# AQ_sensor_GSM.net
KiCad netlist of a schematic drawn in EAGLE
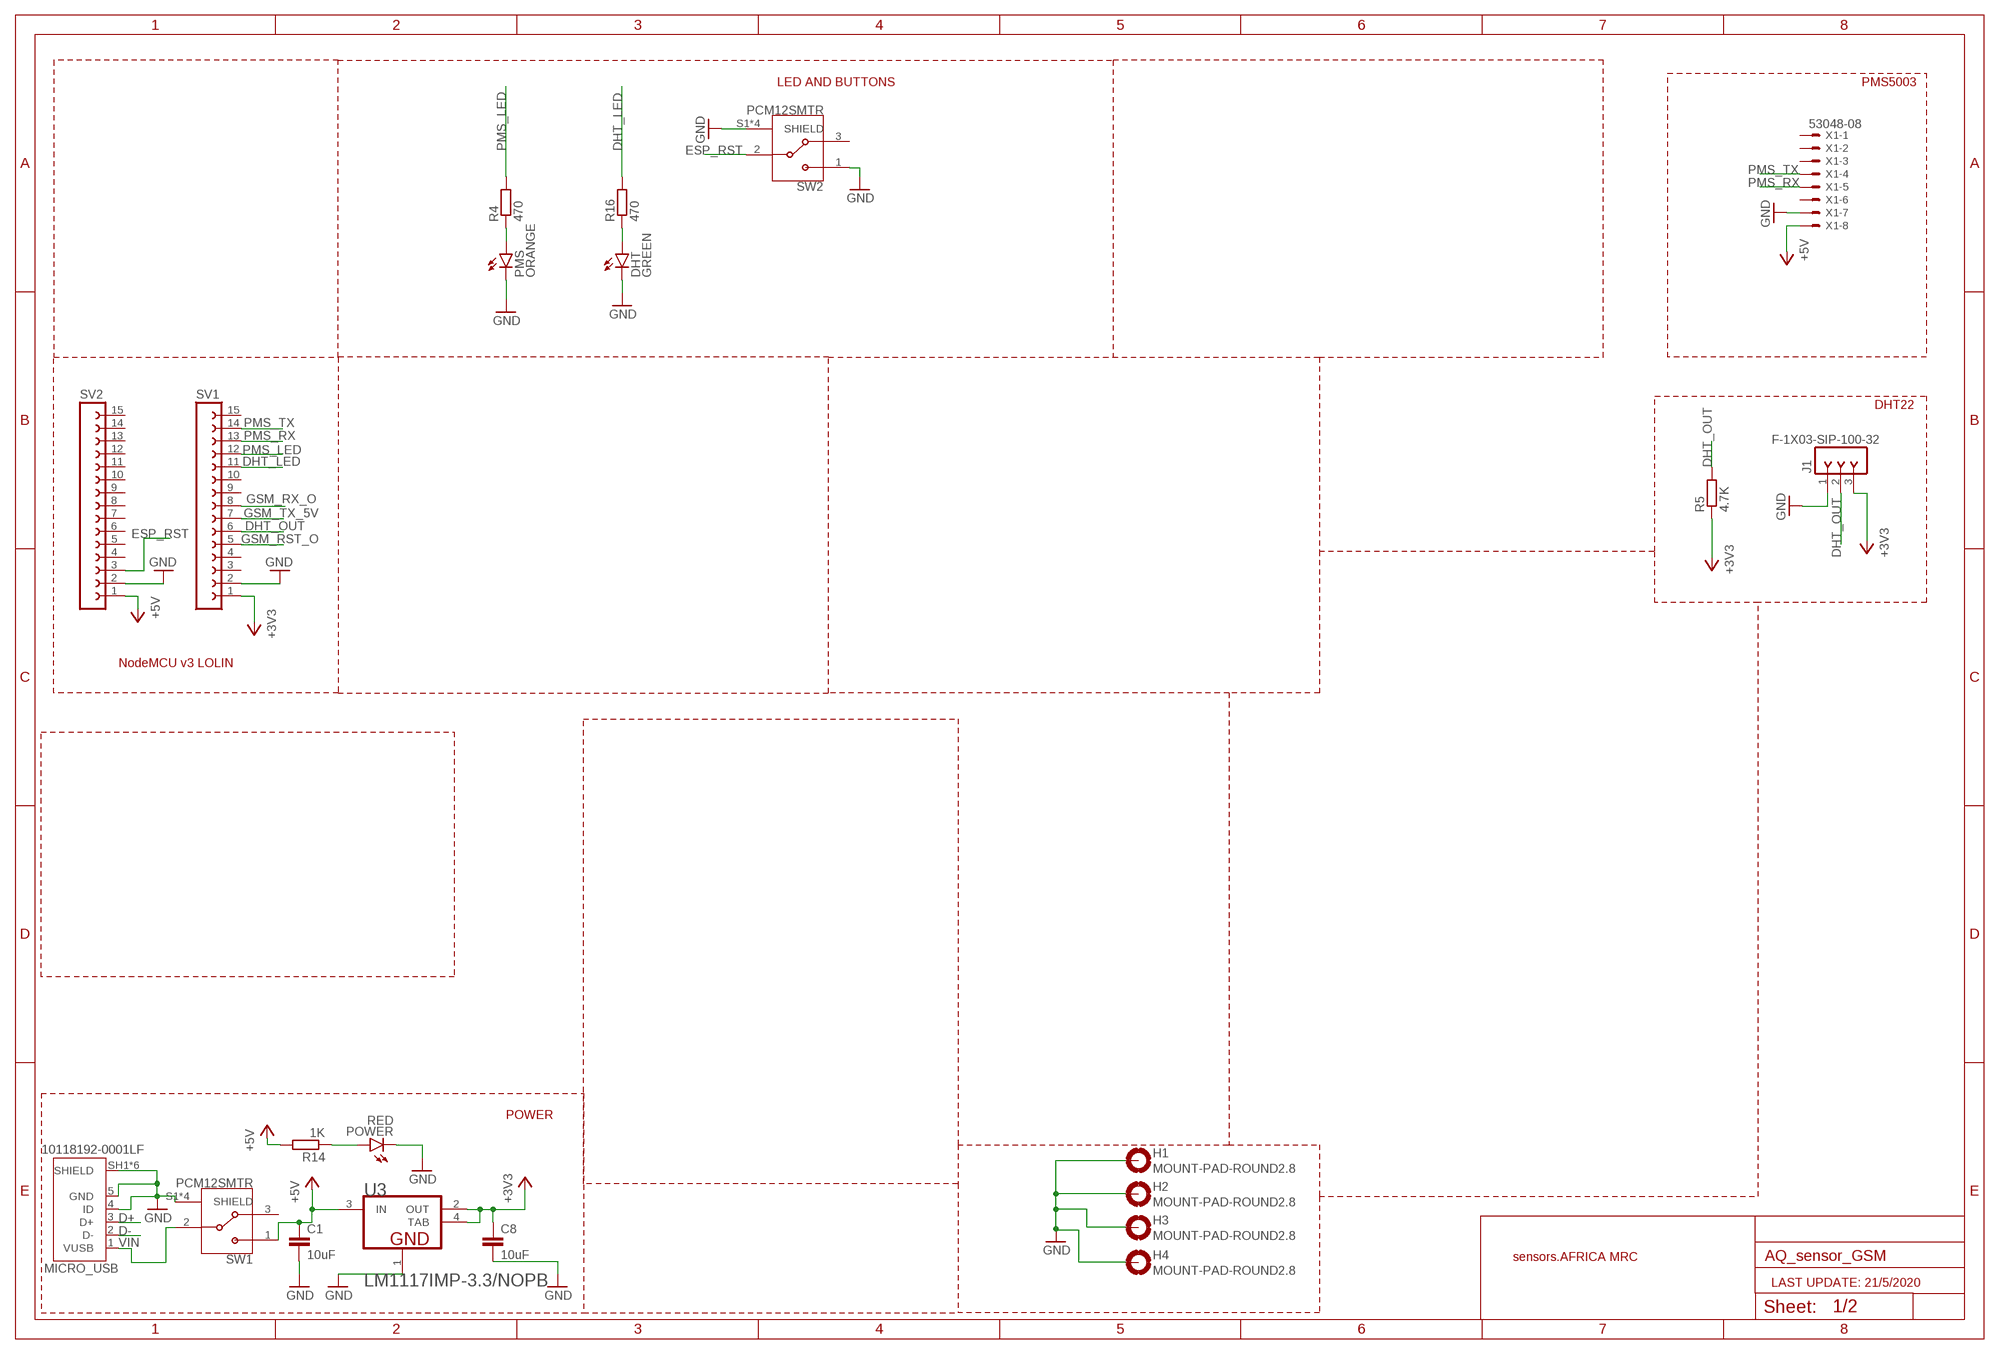
[diagram p0: schematic, sheet 1]
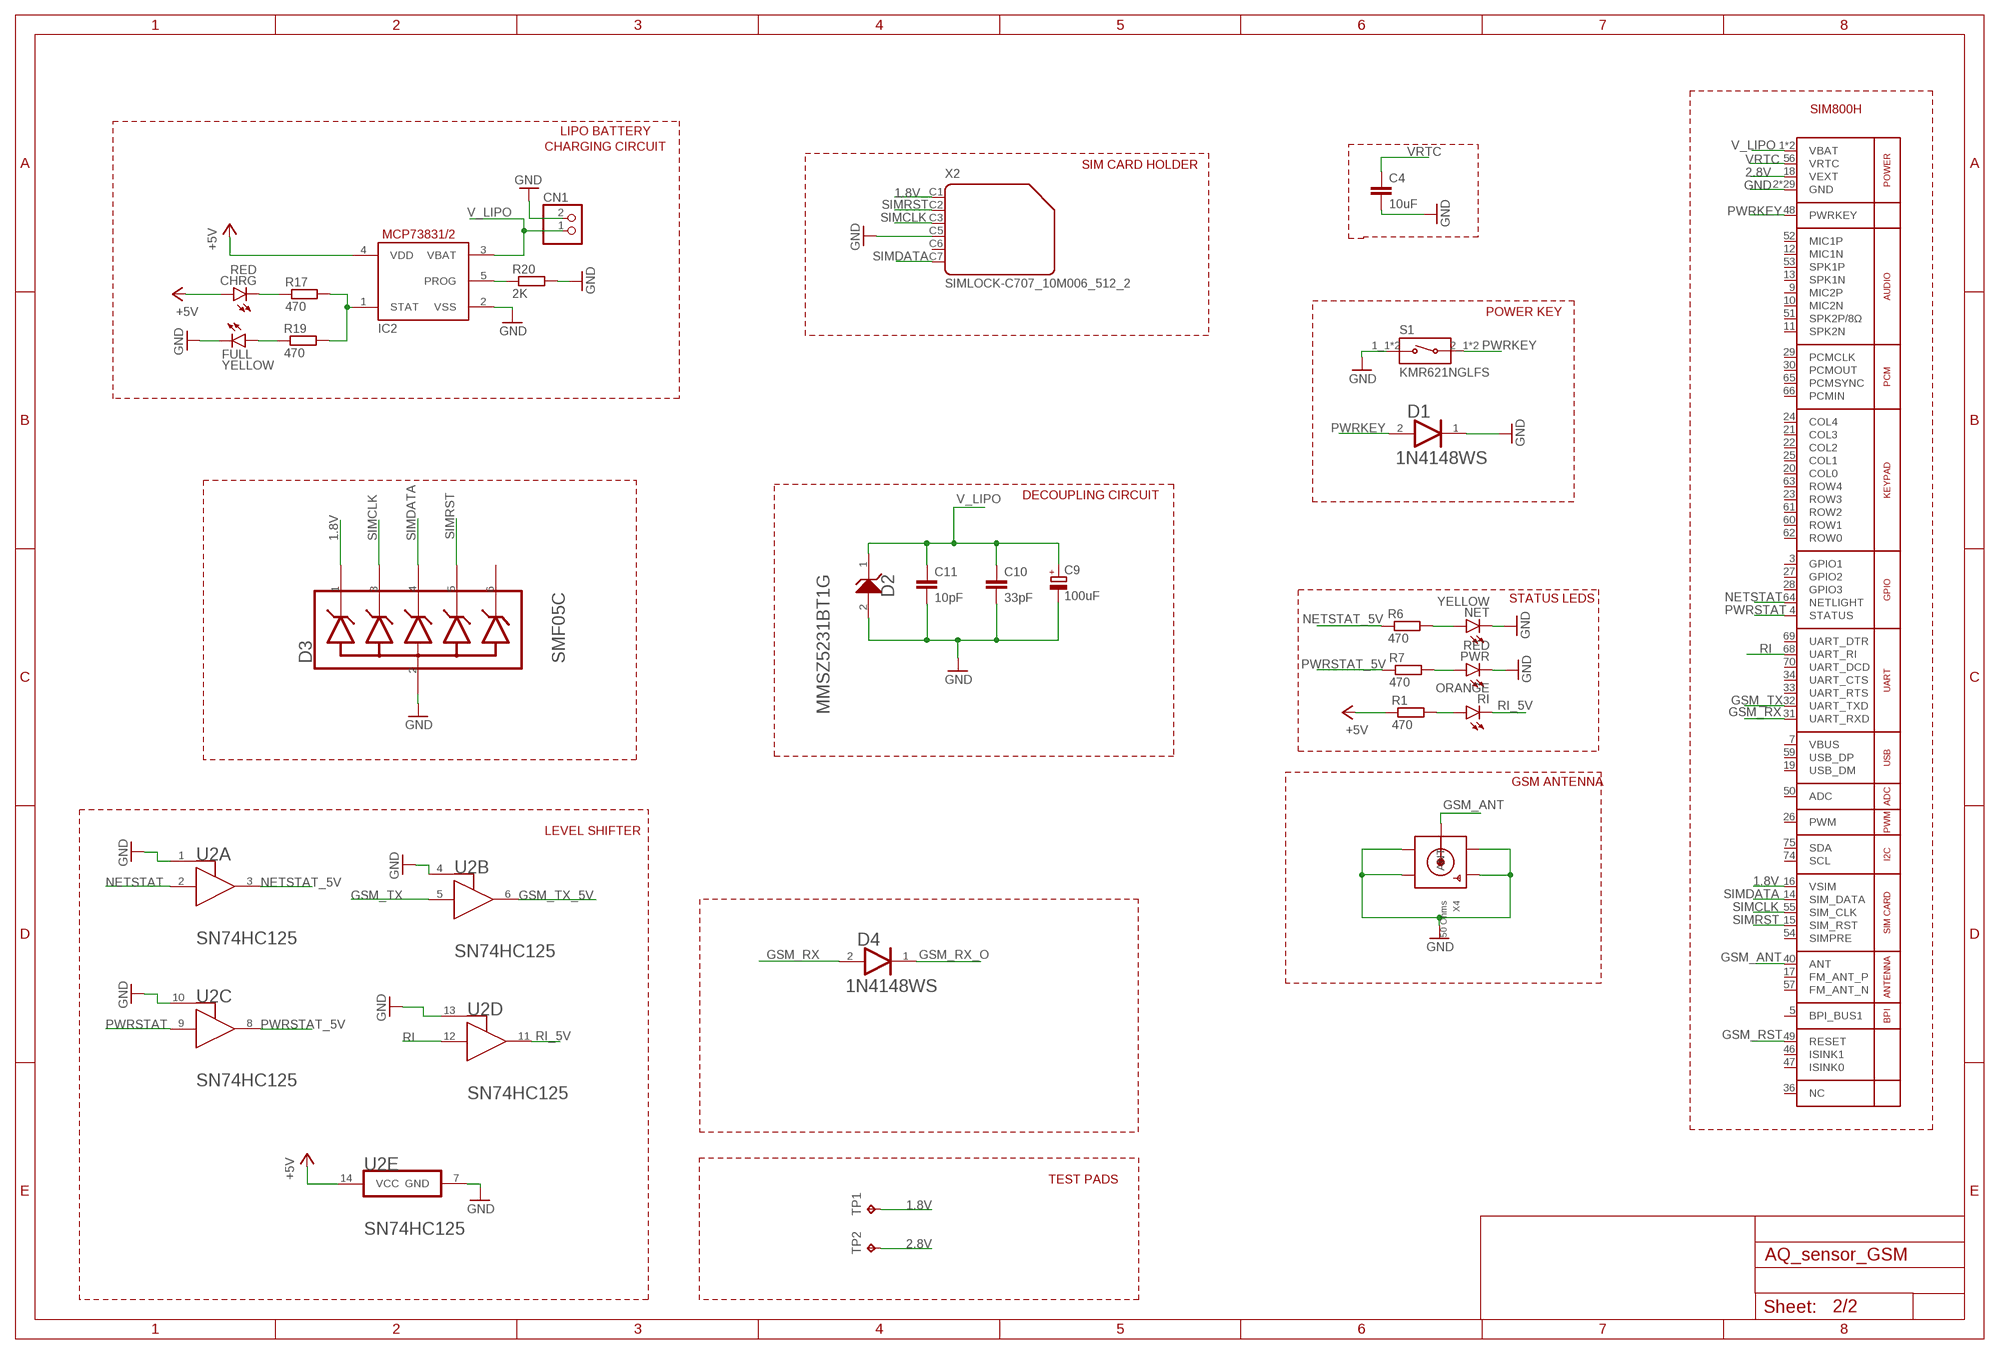
[diagram p1: schematic, sheet 2]

(export (version "E")
  (design (tool "Eeschema 10.0.6"))
  (components
    (comp (ref "C1")
      (value "10uF")
      (footprint "eagle-import:C0603")
      (libsource (lib "eagle-import") (part "C-EUC0603"))
    )
    (comp (ref "C8")
      (value "10uF")
      (footprint "eagle-import:C0603")
      (libsource (lib "eagle-import") (part "C-EUC0603"))
    )
    (comp (ref "DHT")
      (value "GREEN")
      (footprint "eagle-import:CHIP-LED0603")
      (libsource (lib "eagle-import") (part "LEDCHIP-LED0603"))
    )
    (comp (ref "H1")
      (value "MOUNT-PAD-ROUND2.8")
      (footprint "eagle-import:2,8-PAD")
      (libsource (lib "eagle-import") (part "MOUNT-PAD-ROUND2.8"))
    )
    (comp (ref "H2")
      (value "MOUNT-PAD-ROUND2.8")
      (footprint "eagle-import:2,8-PAD")
      (libsource (lib "eagle-import") (part "MOUNT-PAD-ROUND2.8"))
    )
    (comp (ref "H3")
      (value "MOUNT-PAD-ROUND2.8")
      (footprint "eagle-import:2,8-PAD")
      (libsource (lib "eagle-import") (part "MOUNT-PAD-ROUND2.8"))
    )
    (comp (ref "H4")
      (value "MOUNT-PAD-ROUND2.8")
      (footprint "eagle-import:2,8-PAD")
      (libsource (lib "eagle-import") (part "MOUNT-PAD-ROUND2.8"))
    )
    (comp (ref "J1")
      (value "F-1X03-SIP-100-32")
      (footprint "eagle-import:SIP-100-03-32")
      (libsource (lib "eagle-import") (part "F-1X03-SIP-100-32"))
    )
    (comp (ref "MICRO_USB")
      (value "10118192-0001LF")
      (footprint "eagle-import:AMPHENOL_10118192-0001LF")
      (fields (field (name "MF") "Amphenol ICC"))
      (libsource (lib "eagle-import") (part "10118192-0001LF"))
    )
    (comp (ref "PMS")
      (value "ORANGE")
      (footprint "eagle-import:CHIP-LED0603")
      (libsource (lib "eagle-import") (part "LEDCHIP-LED0603"))
    )
    (comp (ref "POWER")
      (value "RED")
      (footprint "eagle-import:CHIP-LED0603")
      (libsource (lib "eagle-import") (part "LEDCHIP-LED0603"))
    )
    (comp (ref "R4")
      (value "470")
      (footprint "eagle-import:R0603")
      (libsource (lib "eagle-import") (part "R-EU_R0603"))
    )
    (comp (ref "R5")
      (value "4.7K")
      (footprint "eagle-import:R0603")
      (libsource (lib "eagle-import") (part "R-EU_R0603"))
    )
    (comp (ref "R14")
      (value "1K")
      (footprint "eagle-import:R0603")
      (libsource (lib "eagle-import") (part "R-EU_R0603"))
    )
    (comp (ref "R16")
      (value "470")
      (footprint "eagle-import:R0603")
      (libsource (lib "eagle-import") (part "R-EU_R0603"))
    )
    (comp (ref "SV1")
      (value "FE15-1")
      (footprint "eagle-import:FE15")
      (libsource (lib "eagle-import") (part "FE15-1"))
    )
    (comp (ref "SV2")
      (value "FE15-1")
      (footprint "eagle-import:FE15")
      (libsource (lib "eagle-import") (part "FE15-1"))
    )
    (comp (ref "SW1")
      (value "PCM12SMTR")
      (footprint "eagle-import:SW_PCM12SMTR")
      (fields (field (name "MF") "C&K"))
      (libsource (lib "eagle-import") (part "PCM12SMTR"))
    )
    (comp (ref "SW2")
      (value "PCM12SMTR")
      (footprint "eagle-import:SW_PCM12SMTR")
      (fields (field (name "MF") "C&K"))
      (libsource (lib "eagle-import") (part "PCM12SMTR"))
    )
    (comp (ref "U3")
      (value "TEXAS_INSTRUMENTS_LM1117IMP-3.3-NOPBTEXAS_INSTRUMENTS_LM1117IMP-3.3-NOPB_0_0")
      (footprint "eagle-import:TEXAS_INSTRUMENTS_LM1117IMP-3.3-NOPB_0")
      (fields (field (name "MF") "Texas Instruments") (field (name "MPN") "LM1117IMP-3.3/NOPB"))
      (libsource (lib "eagle-import") (part "TEXAS_INSTRUMENTS_LM1117IMP-3.3-NOPBTEXAS_INSTRUMENTS_LM1117IMP-3.3-NOPB_0_0"))
    )
    (comp (ref "X1")
      (value "53048-08")
      (footprint "eagle-import:53048-08")
      (fields (field (name "MF") "WALDOM/MOLEX") (field (name "MPN") "53048-0810"))
      (libsource (lib "eagle-import") (part "53?-08048"))
    )
    (comp (ref "C4")
      (value "10uF")
      (footprint "eagle-import:C0603")
      (libsource (lib "eagle-import") (part "C-EUC0603"))
    )
    (comp (ref "C9")
      (value "100uF")
      (footprint "eagle-import:PANASONIC_D")
      (libsource (lib "eagle-import") (part "CPOL-EUD"))
    )
    (comp (ref "C10")
      (value "33pF")
      (footprint "eagle-import:C0603")
      (libsource (lib "eagle-import") (part "C-EUC0603"))
    )
    (comp (ref "C11")
      (value "10pF")
      (footprint "eagle-import:C0603")
      (libsource (lib "eagle-import") (part "C-EUC0603"))
    )
    (comp (ref "CHRG")
      (value "RED")
      (footprint "eagle-import:CHIP-LED0603")
      (libsource (lib "eagle-import") (part "LEDCHIP-LED0603"))
    )
    (comp (ref "CN1")
      (value "JST_2PIN-SMT-RA")
      (footprint "eagle-import:JST-PH-2-SMT-RA")
      (libsource (lib "eagle-import") (part "JST_2PIN-SMT-RA"))
    )
    (comp (ref "D1")
      (value "ON_SEMI_1N4148WSON_SEMI_1N4148WS_0_0")
      (footprint "eagle-import:ON_SEMI_1N4148WS_0")
      (fields
        (field (name "DIGIKEY_PART_NUMBER") "1N4148WSFSCT-ND")
        (field (name "MF") "ON Semi")
        (field (name "MOUSER_PART_NUMBER") "512-1N4148WS")
      )
      (libsource (lib "eagle-import") (part "ON_SEMI_1N4148WSON_SEMI_1N4148WS_0_0"))
    )
    (comp (ref "D2")
      (value "ON_SEMICONDUCTOR_MMSZ5231BT1GON_SEMICONDUCTOR_MMSZ5231BT1G_0_0")
      (footprint "eagle-import:ON_SEMICONDUCTOR_MMSZ5231BT1G_0")
      (fields (field (name "MF") "On Semiconductor") (field (name "MPN") "MMSZ5231BT1G"))
      (libsource (lib "eagle-import") (part "ON_SEMICONDUCTOR_MMSZ5231BT1GON_SEMICONDUCTOR_MMSZ5231BT1G_0_0"))
    )
    (comp (ref "D3")
      (value "SEMTECH_SMF05CSEMTECH_SMF05C_0_0")
      (footprint "eagle-import:SEMTECH_SMF05C_0")
      (fields
        (field (name "DIGIKEY_PART_NUMBER") "SMF05CCT-ND")
        (field (name "MF") "Semtech")
        (field (name "MOUSER_PART_NUMBER") "947-SMF05C.TCT")
      )
      (libsource (lib "eagle-import") (part "SEMTECH_SMF05CSEMTECH_SMF05C_0_0"))
    )
    (comp (ref "D4")
      (value "ON_SEMI_1N4148WSON_SEMI_1N4148WS_0_0")
      (footprint "eagle-import:ON_SEMI_1N4148WS_0")
      (fields
        (field (name "DIGIKEY_PART_NUMBER") "1N4148WSFSCT-ND")
        (field (name "MF") "ON Semi")
        (field (name "MOUSER_PART_NUMBER") "512-1N4148WS")
      )
      (libsource (lib "eagle-import") (part "ON_SEMI_1N4148WSON_SEMI_1N4148WS_0_0"))
    )
    (comp (ref "FULL")
      (value "YELLOW")
      (footprint "eagle-import:CHIP-LED0603")
      (libsource (lib "eagle-import") (part "LEDCHIP-LED0603"))
    )
    (comp (ref "IC2")
      (value "MCP73831/OT")
      (footprint "eagle-import:SOT23-5L")
      (libsource (lib "eagle-import") (part "MCP73831/OT"))
    )
    (comp (ref "NET")
      (value "YELLOW")
      (footprint "eagle-import:CHIP-LED0603")
      (libsource (lib "eagle-import") (part "LEDCHIP-LED0603"))
    )
    (comp (ref "PWR")
      (value "RED")
      (footprint "eagle-import:CHIP-LED0603")
      (libsource (lib "eagle-import") (part "LEDCHIP-LED0603"))
    )
    (comp (ref "R1")
      (value "470")
      (footprint "eagle-import:R0603")
      (libsource (lib "eagle-import") (part "R-EU_R0603"))
    )
    (comp (ref "R6")
      (value "470")
      (footprint "eagle-import:R0603")
      (libsource (lib "eagle-import") (part "R-EU_R0603"))
    )
    (comp (ref "R7")
      (value "470")
      (footprint "eagle-import:R0603")
      (libsource (lib "eagle-import") (part "R-EU_R0603"))
    )
    (comp (ref "R17")
      (value "470")
      (footprint "eagle-import:R0603")
      (libsource (lib "eagle-import") (part "R-EU_R0603"))
    )
    (comp (ref "R19")
      (value "470")
      (footprint "eagle-import:R0603")
      (libsource (lib "eagle-import") (part "R-EU_R0603"))
    )
    (comp (ref "R20")
      (value "2K")
      (footprint "eagle-import:R0603")
      (libsource (lib "eagle-import") (part "R-EU_R0603"))
    )
    (comp (ref "RI")
      (value "ORANGE")
      (footprint "eagle-import:CHIP-LED0603")
      (libsource (lib "eagle-import") (part "LEDCHIP-LED0603"))
    )
    (comp (ref "S1")
      (value "KMR621NGLFS")
      (footprint "eagle-import:SW_KMR621NGLFS")
      (fields (field (name "MF") "C&K") (field (name "MP") "KMR621NG LFS"))
      (libsource (lib "eagle-import") (part "KMR621NGLFS"))
    )
    (comp (ref "TP1")
      (value "TPB1,27")
      (footprint "eagle-import:B1,27")
      (libsource (lib "eagle-import") (part "TPB1,27"))
    )
    (comp (ref "TP2")
      (value "TPB1,27")
      (footprint "eagle-import:B1,27")
      (libsource (lib "eagle-import") (part "TPB1,27"))
    )
    (comp (ref "U1")
      (value "GSM_SIM800L")
      (footprint "eagle-import:SIM800L")
      (libsource (lib "eagle-import") (part "GSM_SIM800L"))
    )
    (comp (ref "U2")
      (value "TEXAS_INSTRUMENTS_SN74HC125TEXAS_INSTRUMENTS_SN74HC125_0_0")
      (footprint "eagle-import:TEXAS_INSTRUMENTS_SN74HC125_0")
      (fields (field (name "MF") "Texas Instruments") (field (name "MPN") "SN74HC125"))
      (libsource (lib "eagle-import") (part "TEXAS_INSTRUMENTS_SN74HC125TEXAS_INSTRUMENTS_SN74HC125_0_0"))
    )
    (comp (ref "X2")
      (value "SIMLOCK-C707_10M006_512_2")
      (footprint "eagle-import:C707_10M006_512_2")
      (libsource (lib "eagle-import") (part "SIMLOCK-C707_10M006_512_2"))
    )
    (comp (ref "X4")
      (value "50 Ohms")
      (footprint "eagle-import:SMA_EDGELAUNCH_UFL")
      (libsource (lib "eagle-import") (part "SMACONNECTOR_EDGE_UFL"))
    )
  )
  (nets
    (net (code "1") (name "+3V3") (class "Default")
      (node (ref "C8") (pin "1") (pinfunction "1_1") (pintype "passive"))
      (node (ref "J1") (pin "3") (pinfunction "3_3") (pintype "passive"))
      (node (ref "R5") (pin "1") (pinfunction "1_1") (pintype "passive"))
      (node (ref "SV1") (pin "1") (pinfunction "1_1") (pintype "passive"))
      (node (ref "U3") (pin "2") (pinfunction "OUT_2") (pintype "power_in"))
      (node (ref "U3") (pin "4") (pinfunction "TAB_4") (pintype "power_in"))
    )
    (net (code "2") (name "+5V") (class "Default")
      (node (ref "C1") (pin "1") (pinfunction "1_1") (pintype "passive"))
      (node (ref "CHRG") (pin "A") (pinfunction "A_A") (pintype "passive"))
      (node (ref "IC2") (pin "4") (pinfunction "VDD_4") (pintype "power_in"))
      (node (ref "R1") (pin "1") (pinfunction "1_1") (pintype "passive"))
      (node (ref "R14") (pin "2") (pinfunction "2_2") (pintype "passive"))
      (node (ref "SV2") (pin "1") (pinfunction "1_1") (pintype "passive"))
      (node (ref "SW1") (pin "1") (pinfunction "1_1") (pintype "passive"))
      (node (ref "U2") (pin "14") (pinfunction "VCC_14") (pintype "power_in"))
      (node (ref "U3") (pin "3") (pinfunction "IN_3") (pintype "power_in"))
      (node (ref "X1") (pin "8") (pinfunction "S_8") (pintype "passive"))
    )
    (net (code "3") (name "1.8V") (class "Default")
      (node (ref "D3") (pin "1") (pinfunction "1_CATHODE_1") (pintype "bidirectional"))
      (node (ref "TP1") (pin "TP") (pinfunction "TP_TP") (pintype "input"))
      (node (ref "U1") (pin "16") (pinfunction "VSIM_16") (pintype "power_in"))
      (node (ref "X2") (pin "C1") (pinfunction "1_C1") (pintype "passive"))
    )
    (net (code "4") (name "2.8V") (class "Default")
      (node (ref "TP2") (pin "TP") (pinfunction "TP_TP") (pintype "input"))
      (node (ref "U1") (pin "18") (pinfunction "VEXT_18") (pintype "power_in"))
    )
    (net (code "5") (name "D+") (class "Default")
      (node (ref "MICRO_USB") (pin "3") (pinfunction "D+_3") (pintype "passive"))
    )
    (net (code "6") (name "D-") (class "Default")
      (node (ref "MICRO_USB") (pin "2") (pinfunction "D-_2") (pintype "passive"))
    )
    (net (code "7") (name "DHT_LED") (class "Default")
      (node (ref "R16") (pin "2") (pinfunction "2_2") (pintype "passive"))
      (node (ref "SV1") (pin "11") (pinfunction "11_11") (pintype "passive"))
    )
    (net (code "8") (name "DHT_OUT") (class "Default")
      (node (ref "J1") (pin "2") (pinfunction "2_2") (pintype "passive"))
      (node (ref "R5") (pin "2") (pinfunction "2_2") (pintype "passive"))
      (node (ref "SV1") (pin "6") (pinfunction "6_6") (pintype "passive"))
    )
    (net (code "9") (name "ESP_RST") (class "Default")
      (node (ref "SV2") (pin "3") (pinfunction "3_3") (pintype "passive"))
      (node (ref "SW2") (pin "2") (pinfunction "2_2") (pintype "passive"))
    )
    (net (code "10") (name "GND") (class "Default")
      (node (ref "C1") (pin "2") (pinfunction "2_2") (pintype "passive"))
      (node (ref "C10") (pin "2") (pinfunction "2_2") (pintype "passive"))
      (node (ref "C11") (pin "2") (pinfunction "2_2") (pintype "passive"))
      (node (ref "C4") (pin "2") (pinfunction "2_2") (pintype "passive"))
      (node (ref "C8") (pin "2") (pinfunction "2_2") (pintype "passive"))
      (node (ref "C9") (pin "-") (pinfunction "-_-") (pintype "passive"))
      (node (ref "CN1") (pin "2") (pinfunction "1_2") (pintype "passive"))
      (node (ref "D1") (pin "1") (pinfunction "CATHODE_1") (pintype "bidirectional"))
      (node (ref "D2") (pin "2") (pinfunction "A_2") (pintype "passive"))
      (node (ref "D3") (pin "2") (pinfunction "ANODE_2") (pintype "bidirectional"))
      (node (ref "DHT") (pin "C") (pinfunction "C_C") (pintype "passive"))
      (node (ref "FULL") (pin "C") (pinfunction "C_C") (pintype "passive"))
      (node (ref "H1") (pin "B2,8") (pinfunction "MOUNT_B2,8") (pintype "passive"))
      (node (ref "H2") (pin "B2,8") (pinfunction "MOUNT_B2,8") (pintype "passive"))
      (node (ref "H3") (pin "B2,8") (pinfunction "MOUNT_B2,8") (pintype "passive"))
      (node (ref "H4") (pin "B2,8") (pinfunction "MOUNT_B2,8") (pintype "passive"))
      (node (ref "IC2") (pin "2") (pinfunction "VSS_2") (pintype "power_in"))
      (node (ref "J1") (pin "1") (pinfunction "1_1") (pintype "passive"))
      (node (ref "MICRO_USB") (pin "4") (pinfunction "ID_4") (pintype "passive"))
      (node (ref "MICRO_USB") (pin "5") (pinfunction "GND_5") (pintype "passive"))
      (node (ref "MICRO_USB") (pin "SH1") (pinfunction "SHIELD_SH1") (pintype "passive"))
      (node (ref "MICRO_USB") (pin "SH2") (pinfunction "SHIELD_SH2") (pintype "passive"))
      (node (ref "MICRO_USB") (pin "SH3") (pinfunction "SHIELD_SH3") (pintype "passive"))
      (node (ref "MICRO_USB") (pin "SH4") (pinfunction "SHIELD_SH4") (pintype "passive"))
      (node (ref "MICRO_USB") (pin "SH5") (pinfunction "SHIELD_SH5") (pintype "passive"))
      (node (ref "MICRO_USB") (pin "SH6") (pinfunction "SHIELD_SH6") (pintype "passive"))
      (node (ref "NET") (pin "C") (pinfunction "C_C") (pintype "passive"))
      (node (ref "PMS") (pin "C") (pinfunction "C_C") (pintype "passive"))
      (node (ref "POWER") (pin "C") (pinfunction "C_C") (pintype "passive"))
      (node (ref "PWR") (pin "C") (pinfunction "C_C") (pintype "passive"))
      (node (ref "R20") (pin "2") (pinfunction "2_2") (pintype "passive"))
      (node (ref "S1") (pin "1_1") (pinfunction "1_1_1") (pintype "passive"))
      (node (ref "S1") (pin "1_2") (pinfunction "1_1_2") (pintype "passive"))
      (node (ref "SV1") (pin "2") (pinfunction "2_2") (pintype "passive"))
      (node (ref "SV2") (pin "2") (pinfunction "2_2") (pintype "passive"))
      (node (ref "SW1") (pin "S1") (pinfunction "SHIELD_S1") (pintype "passive"))
      (node (ref "SW1") (pin "S2") (pinfunction "SHIELD_S2") (pintype "passive"))
      (node (ref "SW1") (pin "S3") (pinfunction "SHIELD_S3") (pintype "passive"))
      (node (ref "SW1") (pin "S4") (pinfunction "SHIELD_S4") (pintype "passive"))
      (node (ref "SW2") (pin "1") (pinfunction "1_1") (pintype "passive"))
      (node (ref "SW2") (pin "S1") (pinfunction "SHIELD_S1") (pintype "passive"))
      (node (ref "SW2") (pin "S2") (pinfunction "SHIELD_S2") (pintype "passive"))
      (node (ref "SW2") (pin "S3") (pinfunction "SHIELD_S3") (pintype "passive"))
      (node (ref "SW2") (pin "S4") (pinfunction "SHIELD_S4") (pintype "passive"))
      (node (ref "U1") (pin "2") (pinfunction "GND_2") (pintype "power_in"))
      (node (ref "U1") (pin "35") (pinfunction "GND_35") (pintype "power_in"))
      (node (ref "U1") (pin "37") (pinfunction "GND_37") (pintype "power_in"))
      (node (ref "U1") (pin "38") (pinfunction "GND_38") (pintype "power_in"))
      (node (ref "U1") (pin "39") (pinfunction "GND_39") (pintype "power_in"))
      (node (ref "U1") (pin "41") (pinfunction "GND_41") (pintype "power_in"))
      (node (ref "U1") (pin "43") (pinfunction "GND_43") (pintype "power_in"))
      (node (ref "U1") (pin "44") (pinfunction "GND_44") (pintype "power_in"))
      (node (ref "U1") (pin "45") (pinfunction "GND_45") (pintype "power_in"))
      (node (ref "U1") (pin "58") (pinfunction "GND_58") (pintype "power_in"))
      (node (ref "U1") (pin "6") (pinfunction "GND_6") (pintype "power_in"))
      (node (ref "U1") (pin "67") (pinfunction "GND_67") (pintype "power_in"))
      (node (ref "U1") (pin "71") (pinfunction "GND_71") (pintype "power_in"))
      (node (ref "U1") (pin "72") (pinfunction "GND_72") (pintype "power_in"))
      (node (ref "U1") (pin "73") (pinfunction "GND_73") (pintype "power_in"))
      (node (ref "U1") (pin "76") (pinfunction "GND_76") (pintype "power_in"))
      (node (ref "U1") (pin "77") (pinfunction "GND_77") (pintype "power_in"))
      (node (ref "U1") (pin "78") (pinfunction "GND_78") (pintype "power_in"))
      (node (ref "U1") (pin "79") (pinfunction "GND_79") (pintype "power_in"))
      (node (ref "U1") (pin "8") (pinfunction "GND_8") (pintype "power_in"))
      (node (ref "U1") (pin "80") (pinfunction "GND_80") (pintype "power_in"))
      (node (ref "U1") (pin "81") (pinfunction "GND_81") (pintype "power_in"))
      (node (ref "U1") (pin "82") (pinfunction "GND_82") (pintype "power_in"))
      (node (ref "U1") (pin "83") (pinfunction "GND_83") (pintype "power_in"))
      (node (ref "U1") (pin "84") (pinfunction "GND_84") (pintype "power_in"))
      (node (ref "U1") (pin "85") (pinfunction "GND_85") (pintype "power_in"))
      (node (ref "U1") (pin "86") (pinfunction "GND_86") (pintype "power_in"))
      (node (ref "U1") (pin "87") (pinfunction "GND_87") (pintype "power_in"))
      (node (ref "U1") (pin "88") (pinfunction "GND_88") (pintype "power_in"))
      (node (ref "U2") (pin "1") (pinfunction "1_~{OE}_1") (pintype "input"))
      (node (ref "U2") (pin "10") (pinfunction "2_~{OE}_10") (pintype "input"))
      (node (ref "U2") (pin "13") (pinfunction "3_~{OE}_13") (pintype "input"))
      (node (ref "U2") (pin "4") (pinfunction "4_~{OE}_4") (pintype "input"))
      (node (ref "U2") (pin "7") (pinfunction "GND_7") (pintype "power_in"))
      (node (ref "U3") (pin "1") (pinfunction "GND_1") (pintype "power_in"))
      (node (ref "X1") (pin "7") (pinfunction "S_7") (pintype "passive"))
      (node (ref "X2") (pin "C5") (pinfunction "4_C5") (pintype "passive"))
      (node (ref "X4") (pin "GND@1") (pinfunction "GND1_GND@1") (pintype "power_in"))
      (node (ref "X4") (pin "GND@2") (pinfunction "GND2_GND@2") (pintype "power_in"))
      (node (ref "X4") (pin "GND@3") (pinfunction "GND3_GND@3") (pintype "power_in"))
      (node (ref "X4") (pin "GND@4") (pinfunction "GND4_GND@4") (pintype "power_in"))
    )
    (net (code "11") (name "GSM_ANT") (class "Default")
      (node (ref "U1") (pin "40") (pinfunction "ANT_40") (pintype "bidirectional"))
      (node (ref "X4") (pin "P") (pinfunction "ANT_P") (pintype "bidirectional"))
    )
    (net (code "12") (name "GSM_RST") (class "Default")
      (node (ref "U1") (pin "49") (pinfunction "RESET_49") (pintype "input"))
    )
    (net (code "13") (name "GSM_RST_O") (class "Default")
      (node (ref "SV1") (pin "5") (pinfunction "5_5") (pintype "passive"))
    )
    (net (code "14") (name "GSM_RX") (class "Default")
      (node (ref "D4") (pin "2") (pinfunction "ANODE_2") (pintype "bidirectional"))
      (node (ref "U1") (pin "31") (pinfunction "UART_RXD_31") (pintype "input"))
    )
    (net (code "15") (name "GSM_RX_O") (class "Default")
      (node (ref "D4") (pin "1") (pinfunction "CATHODE_1") (pintype "bidirectional"))
      (node (ref "SV1") (pin "8") (pinfunction "8_8") (pintype "passive"))
    )
    (net (code "16") (name "GSM_TX") (class "Default")
      (node (ref "U1") (pin "32") (pinfunction "UART_TXD_32") (pintype "output"))
      (node (ref "U2") (pin "5") (pinfunction "2A_5") (pintype "input"))
    )
    (net (code "17") (name "GSM_TX_5V") (class "Default")
      (node (ref "SV1") (pin "7") (pinfunction "7_7") (pintype "passive"))
      (node (ref "U2") (pin "6") (pinfunction "2Y_6") (pintype "tri_state"))
    )
    (net (code "18") (name "NETSTAT") (class "Default")
      (node (ref "U1") (pin "64") (pinfunction "NETLIGHT_64") (pintype "output"))
      (node (ref "U2") (pin "2") (pinfunction "1A_2") (pintype "input"))
    )
    (net (code "19") (name "NETSTAT_5V") (class "Default")
      (node (ref "R6") (pin "1") (pinfunction "1_1") (pintype "passive"))
      (node (ref "U2") (pin "3") (pinfunction "1Y_3") (pintype "tri_state"))
    )
    (net (code "20") (name "Net-(CHRG-PadC)") (class "Default")
      (node (ref "CHRG") (pin "C") (pinfunction "C_C") (pintype "passive"))
      (node (ref "R17") (pin "1") (pinfunction "1_1") (pintype "passive"))
    )
    (net (code "21") (name "Net-(DHT-PadA)") (class "Default")
      (node (ref "DHT") (pin "A") (pinfunction "A_A") (pintype "passive"))
      (node (ref "R16") (pin "1") (pinfunction "1_1") (pintype "passive"))
    )
    (net (code "22") (name "Net-(FULL-PadA)") (class "Default")
      (node (ref "FULL") (pin "A") (pinfunction "A_A") (pintype "passive"))
      (node (ref "R19") (pin "1") (pinfunction "1_1") (pintype "passive"))
    )
    (net (code "23") (name "Net-(IC2-PROG)") (class "Default")
      (node (ref "IC2") (pin "5") (pinfunction "PROG_5") (pintype "input"))
      (node (ref "R20") (pin "1") (pinfunction "1_1") (pintype "passive"))
    )
    (net (code "24") (name "Net-(IC2-STAT)") (class "Default")
      (node (ref "IC2") (pin "1") (pinfunction "STAT_1") (pintype "output"))
      (node (ref "R17") (pin "2") (pinfunction "2_2") (pintype "passive"))
      (node (ref "R19") (pin "2") (pinfunction "2_2") (pintype "passive"))
    )
    (net (code "25") (name "Net-(NET-PadA)") (class "Default")
      (node (ref "NET") (pin "A") (pinfunction "A_A") (pintype "passive"))
      (node (ref "R6") (pin "2") (pinfunction "2_2") (pintype "passive"))
    )
    (net (code "26") (name "Net-(PMS-PadA)") (class "Default")
      (node (ref "PMS") (pin "A") (pinfunction "A_A") (pintype "passive"))
      (node (ref "R4") (pin "1") (pinfunction "1_1") (pintype "passive"))
    )
    (net (code "27") (name "Net-(POWER-PadA)") (class "Default")
      (node (ref "POWER") (pin "A") (pinfunction "A_A") (pintype "passive"))
      (node (ref "R14") (pin "1") (pinfunction "1_1") (pintype "passive"))
    )
    (net (code "28") (name "Net-(PWR-PadA)") (class "Default")
      (node (ref "PWR") (pin "A") (pinfunction "A_A") (pintype "passive"))
      (node (ref "R7") (pin "2") (pinfunction "2_2") (pintype "passive"))
    )
    (net (code "29") (name "Net-(R1-Pad2)") (class "Default")
      (node (ref "R1") (pin "2") (pinfunction "2_2") (pintype "passive"))
      (node (ref "RI") (pin "A") (pinfunction "A_A") (pintype "passive"))
    )
    (net (code "30") (name "PMS_LED") (class "Default")
      (node (ref "R4") (pin "2") (pinfunction "2_2") (pintype "passive"))
      (node (ref "SV1") (pin "12") (pinfunction "12_12") (pintype "passive"))
    )
    (net (code "31") (name "PMS_RX") (class "Default")
      (node (ref "SV1") (pin "13") (pinfunction "13_13") (pintype "passive"))
      (node (ref "X1") (pin "5") (pinfunction "S_5") (pintype "passive"))
    )
    (net (code "32") (name "PMS_TX") (class "Default")
      (node (ref "SV1") (pin "14") (pinfunction "14_14") (pintype "passive"))
      (node (ref "X1") (pin "4") (pinfunction "S_4") (pintype "passive"))
    )
    (net (code "33") (name "PWRKEY") (class "Default")
      (node (ref "D1") (pin "2") (pinfunction "ANODE_2") (pintype "bidirectional"))
      (node (ref "S1") (pin "2_1") (pinfunction "2_2_1") (pintype "passive"))
      (node (ref "S1") (pin "2_2") (pinfunction "2_2_2") (pintype "passive"))
      (node (ref "U1") (pin "48") (pinfunction "PWRKEY_48") (pintype "input"))
    )
    (net (code "34") (name "PWRSTAT") (class "Default")
      (node (ref "U1") (pin "4") (pinfunction "STATUS_4") (pintype "output"))
      (node (ref "U2") (pin "9") (pinfunction "3A_9") (pintype "input"))
    )
    (net (code "35") (name "PWRSTAT_5V") (class "Default")
      (node (ref "R7") (pin "1") (pinfunction "1_1") (pintype "passive"))
      (node (ref "U2") (pin "8") (pinfunction "3Y_8") (pintype "tri_state"))
    )
    (net (code "36") (name "RI") (class "Default")
      (node (ref "U1") (pin "68") (pinfunction "UART_RI_68") (pintype "output"))
      (node (ref "U2") (pin "12") (pinfunction "4A_12") (pintype "input"))
    )
    (net (code "37") (name "RI_5V") (class "Default")
      (node (ref "RI") (pin "C") (pinfunction "C_C") (pintype "passive"))
      (node (ref "U2") (pin "11") (pinfunction "4Y_11") (pintype "tri_state"))
    )
    (net (code "38") (name "SIMCLK") (class "Default")
      (node (ref "D3") (pin "3") (pinfunction "2_CATHODE_3") (pintype "bidirectional"))
      (node (ref "U1") (pin "55") (pinfunction "SIM_CLK_55") (pintype "output"))
      (node (ref "X2") (pin "C3") (pinfunction "3_C3") (pintype "passive"))
    )
    (net (code "39") (name "SIMDATA") (class "Default")
      (node (ref "D3") (pin "4") (pinfunction "3_CATHODE_4") (pintype "bidirectional"))
      (node (ref "U1") (pin "14") (pinfunction "SIM_DATA_14") (pintype "bidirectional"))
      (node (ref "X2") (pin "C7") (pinfunction "6_C7") (pintype "passive"))
    )
    (net (code "40") (name "SIMRST") (class "Default")
      (node (ref "D3") (pin "5") (pinfunction "4_CATHODE_5") (pintype "bidirectional"))
      (node (ref "U1") (pin "15") (pinfunction "SIM_RST_15") (pintype "output"))
      (node (ref "X2") (pin "C2") (pinfunction "2_C2") (pintype "passive"))
    )
    (net (code "41") (name "VBUS") (class "Default")
      (node (ref "U1") (pin "7") (pinfunction "VBUS_7") (pintype "power_in"))
    )
    (net (code "42") (name "VIN") (class "Default")
      (node (ref "MICRO_USB") (pin "1") (pinfunction "VUSB_1") (pintype "passive"))
      (node (ref "SW1") (pin "2") (pinfunction "2_2") (pintype "passive"))
    )
    (net (code "43") (name "VRTC") (class "Default")
      (node (ref "C4") (pin "1") (pinfunction "1_1") (pintype "passive"))
      (node (ref "U1") (pin "56") (pinfunction "VRTC_56") (pintype "power_in"))
    )
    (net (code "44") (name "V_LIPO") (class "Default")
      (node (ref "C10") (pin "1") (pinfunction "1_1") (pintype "passive"))
      (node (ref "C11") (pin "1") (pinfunction "1_1") (pintype "passive"))
      (node (ref "C9") (pin "+") (pinfunction "+_+") (pintype "passive"))
      (node (ref "CN1") (pin "1") (pinfunction "2_1") (pintype "passive"))
      (node (ref "D2") (pin "1") (pinfunction "K_1") (pintype "passive"))
      (node (ref "IC2") (pin "3") (pinfunction "VBAT_3") (pintype "bidirectional"))
      (node (ref "U1") (pin "1") (pinfunction "VBAT_1") (pintype "power_in"))
      (node (ref "U1") (pin "42") (pinfunction "VBAT_42") (pintype "power_in"))
    )
    (net (code "45") (name "unconnected-(D3-5_CATHODE-Pad6)") (class "Default")
      (node (ref "D3") (pin "6") (pinfunction "5_CATHODE_6") (pintype "bidirectional"))
    )
    (net (code "46") (name "unconnected-(SV1-Pad3)") (class "Default")
      (node (ref "SV1") (pin "3") (pinfunction "3_3") (pintype "passive"))
    )
    (net (code "47") (name "unconnected-(SV1-Pad4)") (class "Default")
      (node (ref "SV1") (pin "4") (pinfunction "4_4") (pintype "passive"))
    )
    (net (code "48") (name "unconnected-(SV1-Pad9)") (class "Default")
      (node (ref "SV1") (pin "9") (pinfunction "9_9") (pintype "passive"))
    )
    (net (code "49") (name "unconnected-(SV1-Pad10)") (class "Default")
      (node (ref "SV1") (pin "10") (pinfunction "10_10") (pintype "passive"))
    )
    (net (code "50") (name "unconnected-(SV1-Pad15)") (class "Default")
      (node (ref "SV1") (pin "15") (pinfunction "15_15") (pintype "passive"))
    )
    (net (code "51") (name "unconnected-(SV2-Pad4)") (class "Default")
      (node (ref "SV2") (pin "4") (pinfunction "4_4") (pintype "passive"))
    )
    (net (code "52") (name "unconnected-(SV2-Pad5)") (class "Default")
      (node (ref "SV2") (pin "5") (pinfunction "5_5") (pintype "passive"))
    )
    (net (code "53") (name "unconnected-(SV2-Pad6)") (class "Default")
      (node (ref "SV2") (pin "6") (pinfunction "6_6") (pintype "passive"))
    )
    (net (code "54") (name "unconnected-(SV2-Pad7)") (class "Default")
      (node (ref "SV2") (pin "7") (pinfunction "7_7") (pintype "passive"))
    )
    (net (code "55") (name "unconnected-(SV2-Pad8)") (class "Default")
      (node (ref "SV2") (pin "8") (pinfunction "8_8") (pintype "passive"))
    )
    (net (code "56") (name "unconnected-(SV2-Pad9)") (class "Default")
      (node (ref "SV2") (pin "9") (pinfunction "9_9") (pintype "passive"))
    )
    (net (code "57") (name "unconnected-(SV2-Pad10)") (class "Default")
      (node (ref "SV2") (pin "10") (pinfunction "10_10") (pintype "passive"))
    )
    (net (code "58") (name "unconnected-(SV2-Pad11)") (class "Default")
      (node (ref "SV2") (pin "11") (pinfunction "11_11") (pintype "passive"))
    )
    (net (code "59") (name "unconnected-(SV2-Pad12)") (class "Default")
      (node (ref "SV2") (pin "12") (pinfunction "12_12") (pintype "passive"))
    )
    (net (code "60") (name "unconnected-(SV2-Pad13)") (class "Default")
      (node (ref "SV2") (pin "13") (pinfunction "13_13") (pintype "passive"))
    )
    (net (code "61") (name "unconnected-(SV2-Pad14)") (class "Default")
      (node (ref "SV2") (pin "14") (pinfunction "14_14") (pintype "passive"))
    )
    (net (code "62") (name "unconnected-(SV2-Pad15)") (class "Default")
      (node (ref "SV2") (pin "15") (pinfunction "15_15") (pintype "passive"))
    )
    (net (code "63") (name "unconnected-(SW1-Pad3)") (class "Default")
      (node (ref "SW1") (pin "3") (pinfunction "3_3") (pintype "passive"))
    )
    (net (code "64") (name "unconnected-(SW2-Pad3)") (class "Default")
      (node (ref "SW2") (pin "3") (pinfunction "3_3") (pintype "passive"))
    )
    (net (code "65") (name "unconnected-(U1-ADC-Pad50)") (class "Default")
      (node (ref "U1") (pin "50") (pinfunction "ADC_50") (pintype "input"))
    )
    (net (code "66") (name "unconnected-(U1-BPI_BUS1-Pad5)") (class "Default")
      (node (ref "U1") (pin "5") (pinfunction "BPI_BUS1_5") (pintype "output"))
    )
    (net (code "67") (name "unconnected-(U1-COL0-Pad20)") (class "Default")
      (node (ref "U1") (pin "20") (pinfunction "COL0_20") (pintype "bidirectional"))
    )
    (net (code "68") (name "unconnected-(U1-COL1-Pad25)") (class "Default")
      (node (ref "U1") (pin "25") (pinfunction "COL1_25") (pintype "bidirectional"))
    )
    (net (code "69") (name "unconnected-(U1-COL2-Pad22)") (class "Default")
      (node (ref "U1") (pin "22") (pinfunction "COL2_22") (pintype "bidirectional"))
    )
    (net (code "70") (name "unconnected-(U1-COL3-Pad21)") (class "Default")
      (node (ref "U1") (pin "21") (pinfunction "COL3_21") (pintype "bidirectional"))
    )
    (net (code "71") (name "unconnected-(U1-COL4-Pad24)") (class "Default")
      (node (ref "U1") (pin "24") (pinfunction "COL4_24") (pintype "bidirectional"))
    )
    (net (code "72") (name "unconnected-(U1-FM_ANT_N-Pad57)") (class "Default")
      (node (ref "U1") (pin "57") (pinfunction "FM_ANT_N_57") (pintype "bidirectional"))
    )
    (net (code "73") (name "unconnected-(U1-FM_ANT_P-Pad17)") (class "Default")
      (node (ref "U1") (pin "17") (pinfunction "FM_ANT_P_17") (pintype "bidirectional"))
    )
    (net (code "74") (name "unconnected-(U1-GPIO1-Pad3)") (class "Default")
      (node (ref "U1") (pin "3") (pinfunction "GPIO1_3") (pintype "bidirectional"))
    )
    (net (code "75") (name "unconnected-(U1-GPIO2-Pad27)") (class "Default")
      (node (ref "U1") (pin "27") (pinfunction "GPIO2_27") (pintype "bidirectional"))
    )
    (net (code "76") (name "unconnected-(U1-GPIO3-Pad28)") (class "Default")
      (node (ref "U1") (pin "28") (pinfunction "GPIO3_28") (pintype "bidirectional"))
    )
    (net (code "77") (name "unconnected-(U1-ISINK0-Pad47)") (class "Default")
      (node (ref "U1") (pin "47") (pinfunction "ISINK0_47") (pintype "input"))
    )
    (net (code "78") (name "unconnected-(U1-ISINK1-Pad46)") (class "Default")
      (node (ref "U1") (pin "46") (pinfunction "ISINK1_46") (pintype "input"))
    )
    (net (code "79") (name "unconnected-(U1-MIC1N-Pad12)") (class "Default")
      (node (ref "U1") (pin "12") (pinfunction "MIC1N_12") (pintype "input"))
    )
    (net (code "80") (name "unconnected-(U1-MIC1P-Pad52)") (class "Default")
      (node (ref "U1") (pin "52") (pinfunction "MIC1P_52") (pintype "input"))
    )
    (net (code "81") (name "unconnected-(U1-MIC2N-Pad10)") (class "Default")
      (node (ref "U1") (pin "10") (pinfunction "MIC2N_10") (pintype "input"))
    )
    (net (code "82") (name "unconnected-(U1-MIC2P-Pad9)") (class "Default")
      (node (ref "U1") (pin "9") (pinfunction "MIC2P_9") (pintype "input"))
    )
    (net (code "83") (name "unconnected-(U1-NC-Pad36)") (class "Default")
      (node (ref "U1") (pin "36") (pinfunction "NC_36") (pintype "no_connect"))
    )
    (net (code "84") (name "unconnected-(U1-PCMCLK-Pad29)") (class "Default")
      (node (ref "U1") (pin "29") (pinfunction "PCMCLK_29") (pintype "output"))
    )
    (net (code "85") (name "unconnected-(U1-PCMIN-Pad66)") (class "Default")
      (node (ref "U1") (pin "66") (pinfunction "PCMIN_66") (pintype "input"))
    )
    (net (code "86") (name "unconnected-(U1-PCMOUT-Pad30)") (class "Default")
      (node (ref "U1") (pin "30") (pinfunction "PCMOUT_30") (pintype "output"))
    )
    (net (code "87") (name "unconnected-(U1-PCMSYNC-Pad65)") (class "Default")
      (node (ref "U1") (pin "65") (pinfunction "PCMSYNC_65") (pintype "output"))
    )
    (net (code "88") (name "unconnected-(U1-PWM-Pad26)") (class "Default")
      (node (ref "U1") (pin "26") (pinfunction "PWM_26") (pintype "output"))
    )
    (net (code "89") (name "unconnected-(U1-ROW0-Pad62)") (class "Default")
      (node (ref "U1") (pin "62") (pinfunction "ROW0_62") (pintype "bidirectional"))
    )
    (net (code "90") (name "unconnected-(U1-ROW1-Pad60)") (class "Default")
      (node (ref "U1") (pin "60") (pinfunction "ROW1_60") (pintype "bidirectional"))
    )
    (net (code "91") (name "unconnected-(U1-ROW2-Pad61)") (class "Default")
      (node (ref "U1") (pin "61") (pinfunction "ROW2_61") (pintype "bidirectional"))
    )
    (net (code "92") (name "unconnected-(U1-ROW3-Pad23)") (class "Default")
      (node (ref "U1") (pin "23") (pinfunction "ROW3_23") (pintype "bidirectional"))
    )
    (net (code "93") (name "unconnected-(U1-ROW4-Pad63)") (class "Default")
      (node (ref "U1") (pin "63") (pinfunction "ROW4_63") (pintype "bidirectional"))
    )
    (net (code "94") (name "unconnected-(U1-SCL-Pad74)") (class "Default")
      (node (ref "U1") (pin "74") (pinfunction "SCL_74") (pintype "bidirectional"))
    )
    (net (code "95") (name "unconnected-(U1-SDA-Pad75)") (class "Default")
      (node (ref "U1") (pin "75") (pinfunction "SDA_75") (pintype "bidirectional"))
    )
    (net (code "96") (name "unconnected-(U1-SIMPRE-Pad54)") (class "Default")
      (node (ref "U1") (pin "54") (pinfunction "SIMPRE_54") (pintype "input"))
    )
    (net (code "97") (name "unconnected-(U1-SPK1N-Pad13)") (class "Default")
      (node (ref "U1") (pin "13") (pinfunction "SPK1N_13") (pintype "output"))
    )
    (net (code "98") (name "unconnected-(U1-SPK1P-Pad53)") (class "Default")
      (node (ref "U1") (pin "53") (pinfunction "SPK1P_53") (pintype "output"))
    )
    (net (code "99") (name "unconnected-(U1-SPK2N-Pad11)") (class "Default")
      (node (ref "U1") (pin "11") (pinfunction "SPK2N_11") (pintype "output"))
    )
    (net (code "100") (name "unconnected-(U1-SPK2P{slash}8Ω-Pad51)") (class "Default")
      (node (ref "U1") (pin "51") (pinfunction "SPK2P/8Ω_51") (pintype "output"))
    )
    (net (code "101") (name "unconnected-(U1-UART_CTS-Pad34)") (class "Default")
      (node (ref "U1") (pin "34") (pinfunction "UART_CTS_34") (pintype "output"))
    )
    (net (code "102") (name "unconnected-(U1-UART_DCD-Pad70)") (class "Default")
      (node (ref "U1") (pin "70") (pinfunction "UART_DCD_70") (pintype "input"))
    )
    (net (code "103") (name "unconnected-(U1-UART_DTR-Pad69)") (class "Default")
      (node (ref "U1") (pin "69") (pinfunction "UART_DTR_69") (pintype "input"))
    )
    (net (code "104") (name "unconnected-(U1-UART_RTS-Pad33)") (class "Default")
      (node (ref "U1") (pin "33") (pinfunction "UART_RTS_33") (pintype "input"))
    )
    (net (code "105") (name "unconnected-(U1-USB_DM-Pad19)") (class "Default")
      (node (ref "U1") (pin "19") (pinfunction "USB_DM_19") (pintype "bidirectional"))
    )
    (net (code "106") (name "unconnected-(U1-USB_DP-Pad59)") (class "Default")
      (node (ref "U1") (pin "59") (pinfunction "USB_DP_59") (pintype "bidirectional"))
    )
    (net (code "107") (name "unconnected-(X1A-S-Pad1)") (class "Default")
      (node (ref "X1") (pin "1") (pinfunction "S_1") (pintype "passive"))
    )
    (net (code "108") (name "unconnected-(X1B-S-Pad2)") (class "Default")
      (node (ref "X1") (pin "2") (pinfunction "S_2") (pintype "passive"))
    )
    (net (code "109") (name "unconnected-(X1C-S-Pad3)") (class "Default")
      (node (ref "X1") (pin "3") (pinfunction "S_3") (pintype "passive"))
    )
    (net (code "110") (name "unconnected-(X1F-S-Pad6)") (class "Default")
      (node (ref "X1") (pin "6") (pinfunction "S_6") (pintype "passive"))
    )
    (net (code "111") (name "unconnected-(X2-5-PadC6)") (class "Default")
      (node (ref "X2") (pin "C6") (pinfunction "5_C6") (pintype "passive"))
    )
  )
)
